# v1.net
KiCad netlist of a schematic drawn in EAGLE
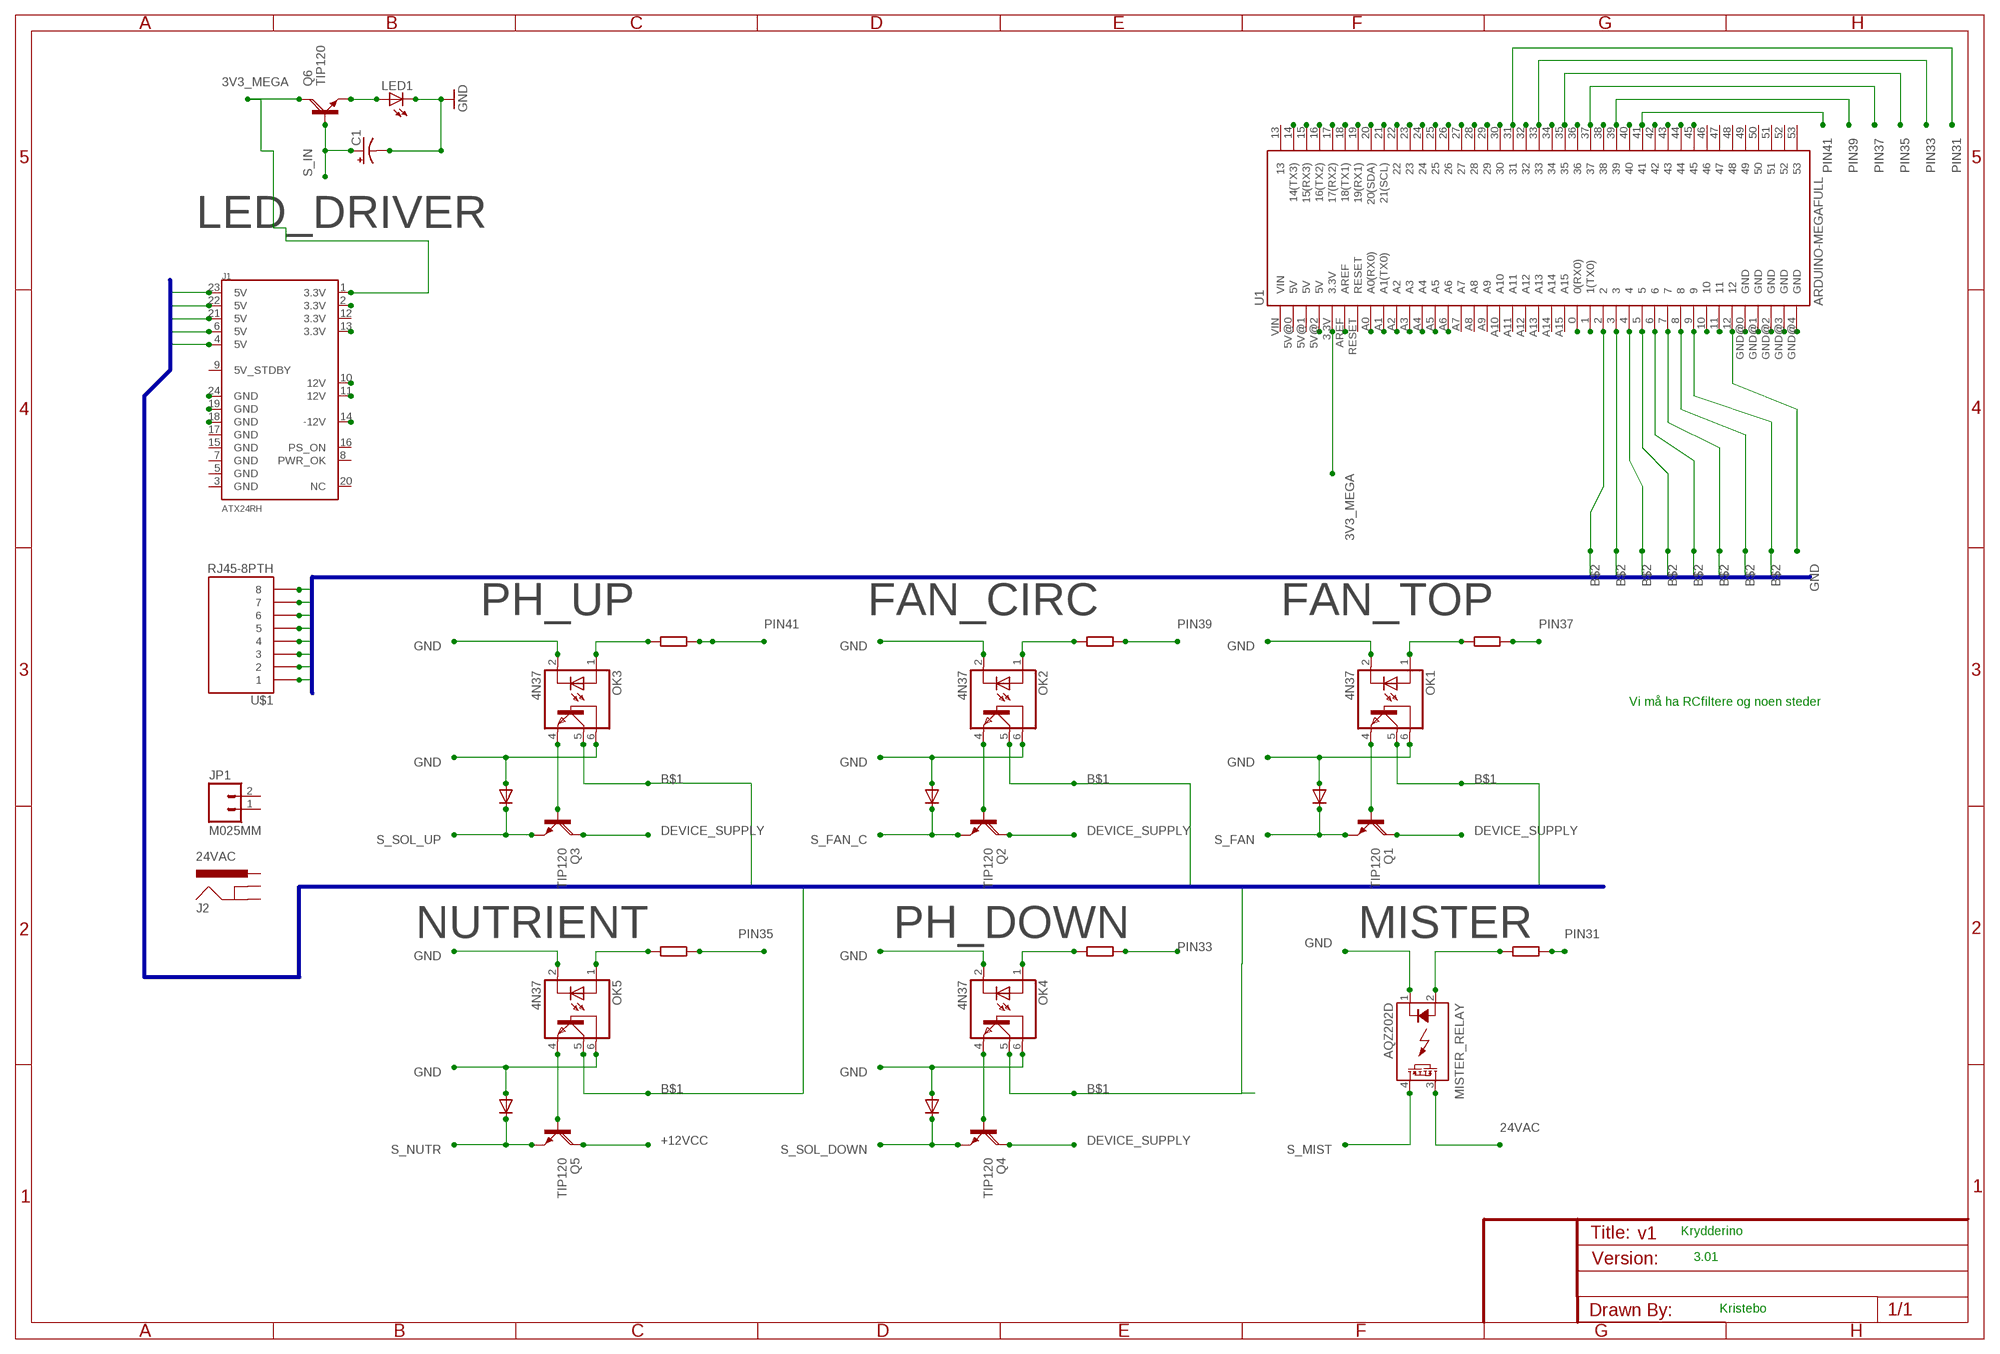
[diagram p0: schematic, sheet 1]

(export (version "E")
  (design (tool "Eeschema 10.0.6"))
  (components
    (comp (ref "C1")
      (value "CAP_POLPTH1")
      (footprint "eagle-import:CPOL-RADIAL-100UF-25V")
      (libsource (lib "eagle-import") (part "CAP_POLPTH1"))
    )
    (comp (ref "J1")
      (value "ATX24RH")
      (footprint "eagle-import:ATX24_RIGHT_ANGLE")
      (libsource (lib "eagle-import") (part "ATX24RH"))
    )
    (comp (ref "J2")
      (value "24VAC")
      (footprint "eagle-import:POWER_JACK_SLOT")
      (libsource (lib "eagle-import") (part "POWER_JACKSLT"))
    )
    (comp (ref "JP1")
      (value "M025MM")
      (footprint "eagle-import:SCREWTERMINAL-5MM-2")
      (libsource (lib "eagle-import") (part "M025MM"))
    )
    (comp (ref "LED1")
      (value "LED3MM")
      (footprint "eagle-import:LED3MM")
      (libsource (lib "eagle-import") (part "LED3MM"))
    )
    (comp (ref "MISTER_RELAY")
      (value "AQZ202D")
      (footprint "eagle-import:AQZ-SIL04")
      (fields (field (name "MF") "AROMAT/ MATSUSHITA"))
      (libsource (lib "eagle-import") (part "AQZ20D2"))
    )
    (comp (ref "OK1")
      (value "4N37")
      (footprint "eagle-import:DIL06")
      (fields (field (name "MF") "FAIRCHILD SEMICONDUCTOR"))
      (libsource (lib "eagle-import") (part "4N37"))
    )
    (comp (ref "OK2")
      (value "4N37")
      (footprint "eagle-import:DIL06")
      (fields (field (name "MF") "FAIRCHILD SEMICONDUCTOR"))
      (libsource (lib "eagle-import") (part "4N37"))
    )
    (comp (ref "OK3")
      (value "4N37")
      (footprint "eagle-import:DIL06")
      (fields (field (name "MF") "FAIRCHILD SEMICONDUCTOR"))
      (libsource (lib "eagle-import") (part "4N37"))
    )
    (comp (ref "OK4")
      (value "4N37")
      (footprint "eagle-import:DIL06")
      (fields (field (name "MF") "FAIRCHILD SEMICONDUCTOR"))
      (libsource (lib "eagle-import") (part "4N37"))
    )
    (comp (ref "OK5")
      (value "4N37")
      (footprint "eagle-import:DIL06")
      (fields (field (name "MF") "FAIRCHILD SEMICONDUCTOR"))
      (libsource (lib "eagle-import") (part "4N37"))
    )
    (comp (ref "Q1")
      (value "TIP120")
      (footprint "eagle-import:TO220AH")
      (libsource (lib "eagle-import") (part "TIP120"))
    )
    (comp (ref "Q2")
      (value "TIP120")
      (footprint "eagle-import:TO220AH")
      (libsource (lib "eagle-import") (part "TIP120"))
    )
    (comp (ref "Q3")
      (value "TIP120")
      (footprint "eagle-import:TO220AH")
      (libsource (lib "eagle-import") (part "TIP120"))
    )
    (comp (ref "Q4")
      (value "TIP120")
      (footprint "eagle-import:TO220AH")
      (libsource (lib "eagle-import") (part "TIP120"))
    )
    (comp (ref "Q5")
      (value "TIP120")
      (footprint "eagle-import:TO220AH")
      (libsource (lib "eagle-import") (part "TIP120"))
    )
    (comp (ref "Q6")
      (value "TIP120")
      (footprint "eagle-import:TO220AH")
      (libsource (lib "eagle-import") (part "TIP120"))
    )
    (comp (ref "U$1")
      (value "RJ45-8PTH")
      (footprint "eagle-import:RJ45-8")
      (libsource (lib "eagle-import") (part "RJ45-8PTH"))
    )
    (comp (ref "U1")
      (value "ARDUINO-MEGAFULL")
      (footprint "eagle-import:ARDUINO_MEGA")
      (libsource (lib "eagle-import") (part "ARDUINO-MEGAFULL"))
    )
  )
  (nets
    (net (code "1") (name "/+12VCC") (class "Default")
      (node (ref "Q5") (pin "C") (pinfunction "C_C") (pintype "passive"))
    )
    (net (code "2") (name "/3V3_MEGA") (class "Default")
      (node (ref "J1") (pin "1") (pinfunction "3.3V_1") (pintype "bidirectional"))
      (node (ref "Q6") (pin "C") (pinfunction "C_C") (pintype "passive"))
      (node (ref "U1") (pin "3.3V") (pinfunction "3.3V_3.3V") (pintype "bidirectional"))
    )
    (net (code "3") (name "/24VAC") (class "Default")
      (node (ref "MISTER_RELAY") (pin "3") (pinfunction "DS1_3") (pintype "passive"))
    )
    (net (code "4") (name "/B$1") (class "Default")
      (node (ref "J1") (pin "21") (pinfunction "5V_21") (pintype "bidirectional"))
      (node (ref "J1") (pin "22") (pinfunction "5V_22") (pintype "bidirectional"))
      (node (ref "J1") (pin "23") (pinfunction "5V_23") (pintype "bidirectional"))
      (node (ref "J1") (pin "4") (pinfunction "5V_4") (pintype "bidirectional"))
      (node (ref "J1") (pin "6") (pinfunction "5V_6") (pintype "bidirectional"))
      (node (ref "OK1") (pin "5") (pinfunction "COL_5") (pintype "passive"))
      (node (ref "OK2") (pin "5") (pinfunction "COL_5") (pintype "passive"))
      (node (ref "OK3") (pin "5") (pinfunction "COL_5") (pintype "passive"))
      (node (ref "OK4") (pin "5") (pinfunction "COL_5") (pintype "passive"))
      (node (ref "OK5") (pin "5") (pinfunction "COL_5") (pintype "passive"))
    )
    (net (code "5") (name "/B$2") (class "Default")
      (node (ref "U$1") (pin "1") (pinfunction "1_1") (pintype "bidirectional"))
      (node (ref "U$1") (pin "2") (pinfunction "2_2") (pintype "bidirectional"))
      (node (ref "U$1") (pin "3") (pinfunction "3_3") (pintype "bidirectional"))
      (node (ref "U$1") (pin "4") (pinfunction "4_4") (pintype "bidirectional"))
      (node (ref "U$1") (pin "5") (pinfunction "5_5") (pintype "bidirectional"))
      (node (ref "U$1") (pin "6") (pinfunction "6_6") (pintype "bidirectional"))
      (node (ref "U$1") (pin "7") (pinfunction "7_7") (pintype "bidirectional"))
      (node (ref "U$1") (pin "8") (pinfunction "8_8") (pintype "bidirectional"))
      (node (ref "U1") (pin "2") (pinfunction "2_2") (pintype "bidirectional"))
      (node (ref "U1") (pin "3") (pinfunction "3_3") (pintype "bidirectional"))
      (node (ref "U1") (pin "4") (pinfunction "4_4") (pintype "bidirectional"))
      (node (ref "U1") (pin "5") (pinfunction "5_5") (pintype "bidirectional"))
      (node (ref "U1") (pin "6") (pinfunction "6_6") (pintype "bidirectional"))
      (node (ref "U1") (pin "7") (pinfunction "7_7") (pintype "bidirectional"))
      (node (ref "U1") (pin "8") (pinfunction "8_8") (pintype "bidirectional"))
      (node (ref "U1") (pin "9") (pinfunction "9_9") (pintype "bidirectional"))
    )
    (net (code "6") (name "/DEVICE_SUPPLY") (class "Default")
      (node (ref "Q1") (pin "C") (pinfunction "C_C") (pintype "passive"))
      (node (ref "Q2") (pin "C") (pinfunction "C_C") (pintype "passive"))
      (node (ref "Q3") (pin "C") (pinfunction "C_C") (pintype "passive"))
      (node (ref "Q4") (pin "C") (pinfunction "C_C") (pintype "passive"))
    )
    (net (code "7") (name "/PIN31") (class "Default")
      (node (ref "OK1") (pin "1") (pinfunction "A_1") (pintype "passive"))
      (node (ref "U1") (pin "31") (pinfunction "31_31") (pintype "bidirectional"))
    )
    (net (code "8") (name "/PIN33") (class "Default")
      (node (ref "OK2") (pin "1") (pinfunction "A_1") (pintype "passive"))
      (node (ref "U1") (pin "33") (pinfunction "33_33") (pintype "bidirectional"))
    )
    (net (code "9") (name "/PIN35") (class "Default")
      (node (ref "OK3") (pin "1") (pinfunction "A_1") (pintype "passive"))
      (node (ref "U1") (pin "35") (pinfunction "35_35") (pintype "bidirectional"))
    )
    (net (code "10") (name "/PIN37") (class "Default")
      (node (ref "OK4") (pin "1") (pinfunction "A_1") (pintype "passive"))
      (node (ref "U1") (pin "37") (pinfunction "37_37") (pintype "bidirectional"))
    )
    (net (code "11") (name "/PIN39") (class "Default")
      (node (ref "OK5") (pin "1") (pinfunction "A_1") (pintype "passive"))
      (node (ref "U1") (pin "39") (pinfunction "39_39") (pintype "bidirectional"))
    )
    (net (code "12") (name "/PIN41") (class "Default")
      (node (ref "MISTER_RELAY") (pin "2") (pinfunction "A_2") (pintype "passive"))
      (node (ref "U1") (pin "41") (pinfunction "41_41") (pintype "bidirectional"))
    )
    (net (code "13") (name "/S_FAN") (class "Default")
      (node (ref "Q1") (pin "E") (pinfunction "E_E") (pintype "passive"))
    )
    (net (code "14") (name "/S_FAN_C") (class "Default")
      (node (ref "Q2") (pin "E") (pinfunction "E_E") (pintype "passive"))
    )
    (net (code "15") (name "/S_IN") (class "Default")
      (node (ref "C1") (pin "1") (pinfunction "+_1") (pintype "passive"))
      (node (ref "Q6") (pin "B") (pinfunction "B_B") (pintype "passive"))
    )
    (net (code "16") (name "/S_MIST") (class "Default")
      (node (ref "MISTER_RELAY") (pin "4") (pinfunction "DS2_4") (pintype "passive"))
    )
    (net (code "17") (name "/S_NUTR") (class "Default")
      (node (ref "Q5") (pin "E") (pinfunction "E_E") (pintype "passive"))
    )
    (net (code "18") (name "/S_SOL_DOWN") (class "Default")
      (node (ref "Q4") (pin "E") (pinfunction "E_E") (pintype "passive"))
    )
    (net (code "19") (name "/S_SOL_UP") (class "Default")
      (node (ref "Q3") (pin "E") (pinfunction "E_E") (pintype "passive"))
    )
    (net (code "20") (name "GND") (class "Default")
      (node (ref "C1") (pin "2") (pinfunction "-_2") (pintype "passive"))
      (node (ref "LED1") (pin "K") (pinfunction "C_K") (pintype "passive"))
      (node (ref "MISTER_RELAY") (pin "1") (pinfunction "K_1") (pintype "passive"))
      (node (ref "OK1") (pin "2") (pinfunction "C_2") (pintype "passive"))
      (node (ref "OK1") (pin "6") (pinfunction "BAS_6") (pintype "passive"))
      (node (ref "OK2") (pin "2") (pinfunction "C_2") (pintype "passive"))
      (node (ref "OK2") (pin "6") (pinfunction "BAS_6") (pintype "passive"))
      (node (ref "OK3") (pin "2") (pinfunction "C_2") (pintype "passive"))
      (node (ref "OK3") (pin "6") (pinfunction "BAS_6") (pintype "passive"))
      (node (ref "OK4") (pin "2") (pinfunction "C_2") (pintype "passive"))
      (node (ref "OK4") (pin "6") (pinfunction "BAS_6") (pintype "passive"))
      (node (ref "OK5") (pin "2") (pinfunction "C_2") (pintype "passive"))
      (node (ref "OK5") (pin "6") (pinfunction "BAS_6") (pintype "passive"))
      (node (ref "U1") (pin "12") (pinfunction "12_12") (pintype "bidirectional"))
    )
    (net (code "21") (name "Net-(LED1-PadA)") (class "Default")
      (node (ref "LED1") (pin "A") (pinfunction "A_A") (pintype "passive"))
      (node (ref "Q6") (pin "E") (pinfunction "E_E") (pintype "passive"))
    )
    (net (code "22") (name "Net-(OK1-EMI)") (class "Default")
      (node (ref "OK1") (pin "4") (pinfunction "EMI_4") (pintype "passive"))
      (node (ref "Q1") (pin "B") (pinfunction "B_B") (pintype "passive"))
    )
    (net (code "23") (name "Net-(OK2-EMI)") (class "Default")
      (node (ref "OK2") (pin "4") (pinfunction "EMI_4") (pintype "passive"))
      (node (ref "Q2") (pin "B") (pinfunction "B_B") (pintype "passive"))
    )
    (net (code "24") (name "Net-(OK3-EMI)") (class "Default")
      (node (ref "OK3") (pin "4") (pinfunction "EMI_4") (pintype "passive"))
      (node (ref "Q3") (pin "B") (pinfunction "B_B") (pintype "passive"))
    )
    (net (code "25") (name "Net-(OK4-EMI)") (class "Default")
      (node (ref "OK4") (pin "4") (pinfunction "EMI_4") (pintype "passive"))
      (node (ref "Q4") (pin "B") (pinfunction "B_B") (pintype "passive"))
    )
    (net (code "26") (name "Net-(OK5-EMI)") (class "Default")
      (node (ref "OK5") (pin "4") (pinfunction "EMI_4") (pintype "passive"))
      (node (ref "Q5") (pin "B") (pinfunction "B_B") (pintype "passive"))
    )
    (net (code "27") (name "unconnected-(J1--12V-Pad14)") (class "Default")
      (node (ref "J1") (pin "14") (pinfunction "-12V_14") (pintype "bidirectional"))
    )
    (net (code "28") (name "unconnected-(J1-3.3V-Pad2)") (class "Default")
      (node (ref "J1") (pin "2") (pinfunction "3.3V_2") (pintype "bidirectional"))
    )
    (net (code "29") (name "unconnected-(J1-3.3V-Pad12)") (class "Default")
      (node (ref "J1") (pin "12") (pinfunction "3.3V_12") (pintype "bidirectional"))
    )
    (net (code "30") (name "unconnected-(J1-3.3V-Pad13)") (class "Default")
      (node (ref "J1") (pin "13") (pinfunction "3.3V_13") (pintype "bidirectional"))
    )
    (net (code "31") (name "unconnected-(J1-5V_STDBY-Pad9)") (class "Default")
      (node (ref "J1") (pin "9") (pinfunction "5V_STDBY_9") (pintype "bidirectional"))
    )
    (net (code "32") (name "unconnected-(J1-12V-Pad10)") (class "Default")
      (node (ref "J1") (pin "10") (pinfunction "12V_10") (pintype "bidirectional"))
    )
    (net (code "33") (name "unconnected-(J1-12V-Pad11)") (class "Default")
      (node (ref "J1") (pin "11") (pinfunction "12V_11") (pintype "bidirectional"))
    )
    (net (code "34") (name "unconnected-(J1-GND-Pad3)") (class "Default")
      (node (ref "J1") (pin "3") (pinfunction "GND_3") (pintype "bidirectional"))
    )
    (net (code "35") (name "unconnected-(J1-GND-Pad5)") (class "Default")
      (node (ref "J1") (pin "5") (pinfunction "GND_5") (pintype "bidirectional"))
    )
    (net (code "36") (name "unconnected-(J1-GND-Pad7)") (class "Default")
      (node (ref "J1") (pin "7") (pinfunction "GND_7") (pintype "bidirectional"))
    )
    (net (code "37") (name "unconnected-(J1-GND-Pad15)") (class "Default")
      (node (ref "J1") (pin "15") (pinfunction "GND_15") (pintype "bidirectional"))
    )
    (net (code "38") (name "unconnected-(J1-GND-Pad17)") (class "Default")
      (node (ref "J1") (pin "17") (pinfunction "GND_17") (pintype "bidirectional"))
    )
    (net (code "39") (name "unconnected-(J1-GND-Pad18)") (class "Default")
      (node (ref "J1") (pin "18") (pinfunction "GND_18") (pintype "bidirectional"))
    )
    (net (code "40") (name "unconnected-(J1-GND-Pad19)") (class "Default")
      (node (ref "J1") (pin "19") (pinfunction "GND_19") (pintype "bidirectional"))
    )
    (net (code "41") (name "unconnected-(J1-GND-Pad24)") (class "Default")
      (node (ref "J1") (pin "24") (pinfunction "GND_24") (pintype "bidirectional"))
    )
    (net (code "42") (name "unconnected-(J1-NC-Pad20)") (class "Default")
      (node (ref "J1") (pin "20") (pinfunction "NC_20") (pintype "bidirectional"))
    )
    (net (code "43") (name "unconnected-(J1-PS_ON-Pad16)") (class "Default")
      (node (ref "J1") (pin "16") (pinfunction "PS_ON_16") (pintype "bidirectional"))
    )
    (net (code "44") (name "unconnected-(J1-PWR_OK-Pad8)") (class "Default")
      (node (ref "J1") (pin "8") (pinfunction "PWR_OK_8") (pintype "bidirectional"))
    )
    (net (code "45") (name "unconnected-(J2-GND-PadGND@2)") (class "Default")
      (node (ref "J2") (pin "GND@2") (pinfunction "GND_GND@2") (pintype "bidirectional"))
    )
    (net (code "46") (name "unconnected-(J2-GNDBREAK-PadGND@1)") (class "Default")
      (node (ref "J2") (pin "GND@1") (pinfunction "GNDBREAK_GND@1") (pintype "bidirectional"))
    )
    (net (code "47") (name "unconnected-(J2-PadPWR)") (class "Default")
      (node (ref "J2") (pin "PWR") (pinfunction "PWR_PWR") (pintype "bidirectional"))
    )
    (net (code "48") (name "unconnected-(JP1-Pad1)") (class "Default")
      (node (ref "JP1") (pin "1") (pinfunction "1_1") (pintype "passive"))
    )
    (net (code "49") (name "unconnected-(JP1-Pad2)") (class "Default")
      (node (ref "JP1") (pin "2") (pinfunction "2_2") (pintype "passive"))
    )
    (net (code "50") (name "unconnected-(U1-0(RX0)-Pad0)") (class "Default")
      (node (ref "U1") (pin "0") (pinfunction "0(RX0)_0") (pintype "bidirectional"))
    )
    (net (code "51") (name "unconnected-(U1-1(TX0)-Pad1)") (class "Default")
      (node (ref "U1") (pin "1") (pinfunction "1(TX0)_1") (pintype "bidirectional"))
    )
    (net (code "52") (name "unconnected-(U1-5V-Pad5V@0)") (class "Default")
      (node (ref "U1") (pin "5V@0") (pinfunction "5V_5V@0") (pintype "bidirectional"))
    )
    (net (code "53") (name "unconnected-(U1-5V-Pad5V@1)") (class "Default")
      (node (ref "U1") (pin "5V@1") (pinfunction "5V_5V@1") (pintype "bidirectional"))
    )
    (net (code "54") (name "unconnected-(U1-5V-Pad5V@2)") (class "Default")
      (node (ref "U1") (pin "5V@2") (pinfunction "5V_5V@2") (pintype "bidirectional"))
    )
    (net (code "55") (name "unconnected-(U1-14(TX3)-Pad14)") (class "Default")
      (node (ref "U1") (pin "14") (pinfunction "14(TX3)_14") (pintype "bidirectional"))
    )
    (net (code "56") (name "unconnected-(U1-15(RX3)-Pad15)") (class "Default")
      (node (ref "U1") (pin "15") (pinfunction "15(RX3)_15") (pintype "bidirectional"))
    )
    (net (code "57") (name "unconnected-(U1-16(TX2)-Pad16)") (class "Default")
      (node (ref "U1") (pin "16") (pinfunction "16(TX2)_16") (pintype "bidirectional"))
    )
    (net (code "58") (name "unconnected-(U1-17(RX2)-Pad17)") (class "Default")
      (node (ref "U1") (pin "17") (pinfunction "17(RX2)_17") (pintype "bidirectional"))
    )
    (net (code "59") (name "unconnected-(U1-18(TX1)-Pad18)") (class "Default")
      (node (ref "U1") (pin "18") (pinfunction "18(TX1)_18") (pintype "bidirectional"))
    )
    (net (code "60") (name "unconnected-(U1-19(RX1)-Pad19)") (class "Default")
      (node (ref "U1") (pin "19") (pinfunction "19(RX1)_19") (pintype "bidirectional"))
    )
    (net (code "61") (name "unconnected-(U1-20(SDA)-Pad20)") (class "Default")
      (node (ref "U1") (pin "20") (pinfunction "20(SDA)_20") (pintype "bidirectional"))
    )
    (net (code "62") (name "unconnected-(U1-21(SCL)-Pad21)") (class "Default")
      (node (ref "U1") (pin "21") (pinfunction "21(SCL)_21") (pintype "bidirectional"))
    )
    (net (code "63") (name "unconnected-(U1-A0(RX0)-PadA0)") (class "Default")
      (node (ref "U1") (pin "A0") (pinfunction "A0(RX0)_A0") (pintype "bidirectional"))
    )
    (net (code "64") (name "unconnected-(U1-A1(TX0)-PadA1)") (class "Default")
      (node (ref "U1") (pin "A1") (pinfunction "A1(TX0)_A1") (pintype "bidirectional"))
    )
    (net (code "65") (name "unconnected-(U1-GND-PadGND@0)") (class "Default")
      (node (ref "U1") (pin "GND@0") (pinfunction "GND_GND@0") (pintype "bidirectional"))
    )
    (net (code "66") (name "unconnected-(U1-GND-PadGND@1)") (class "Default")
      (node (ref "U1") (pin "GND@1") (pinfunction "GND_GND@1") (pintype "bidirectional"))
    )
    (net (code "67") (name "unconnected-(U1-GND-PadGND@2)") (class "Default")
      (node (ref "U1") (pin "GND@2") (pinfunction "GND_GND@2") (pintype "bidirectional"))
    )
    (net (code "68") (name "unconnected-(U1-GND-PadGND@3)") (class "Default")
      (node (ref "U1") (pin "GND@3") (pinfunction "GND_GND@3") (pintype "bidirectional"))
    )
    (net (code "69") (name "unconnected-(U1-GND-PadGND@4)") (class "Default")
      (node (ref "U1") (pin "GND@4") (pinfunction "GND_GND@4") (pintype "bidirectional"))
    )
    (net (code "70") (name "unconnected-(U1-Pad10)") (class "Default")
      (node (ref "U1") (pin "10") (pinfunction "10_10") (pintype "bidirectional"))
    )
    (net (code "71") (name "unconnected-(U1-Pad11)") (class "Default")
      (node (ref "U1") (pin "11") (pinfunction "11_11") (pintype "bidirectional"))
    )
    (net (code "72") (name "unconnected-(U1-Pad13)") (class "Default")
      (node (ref "U1") (pin "13") (pinfunction "13_13") (pintype "bidirectional"))
    )
    (net (code "73") (name "unconnected-(U1-Pad22)") (class "Default")
      (node (ref "U1") (pin "22") (pinfunction "22_22") (pintype "bidirectional"))
    )
    (net (code "74") (name "unconnected-(U1-Pad23)") (class "Default")
      (node (ref "U1") (pin "23") (pinfunction "23_23") (pintype "bidirectional"))
    )
    (net (code "75") (name "unconnected-(U1-Pad24)") (class "Default")
      (node (ref "U1") (pin "24") (pinfunction "24_24") (pintype "bidirectional"))
    )
    (net (code "76") (name "unconnected-(U1-Pad25)") (class "Default")
      (node (ref "U1") (pin "25") (pinfunction "25_25") (pintype "bidirectional"))
    )
    (net (code "77") (name "unconnected-(U1-Pad26)") (class "Default")
      (node (ref "U1") (pin "26") (pinfunction "26_26") (pintype "bidirectional"))
    )
    (net (code "78") (name "unconnected-(U1-Pad27)") (class "Default")
      (node (ref "U1") (pin "27") (pinfunction "27_27") (pintype "bidirectional"))
    )
    (net (code "79") (name "unconnected-(U1-Pad28)") (class "Default")
      (node (ref "U1") (pin "28") (pinfunction "28_28") (pintype "bidirectional"))
    )
    (net (code "80") (name "unconnected-(U1-Pad29)") (class "Default")
      (node (ref "U1") (pin "29") (pinfunction "29_29") (pintype "bidirectional"))
    )
    (net (code "81") (name "unconnected-(U1-Pad30)") (class "Default")
      (node (ref "U1") (pin "30") (pinfunction "30_30") (pintype "bidirectional"))
    )
    (net (code "82") (name "unconnected-(U1-Pad32)") (class "Default")
      (node (ref "U1") (pin "32") (pinfunction "32_32") (pintype "bidirectional"))
    )
    (net (code "83") (name "unconnected-(U1-Pad34)") (class "Default")
      (node (ref "U1") (pin "34") (pinfunction "34_34") (pintype "bidirectional"))
    )
    (net (code "84") (name "unconnected-(U1-Pad36)") (class "Default")
      (node (ref "U1") (pin "36") (pinfunction "36_36") (pintype "bidirectional"))
    )
    (net (code "85") (name "unconnected-(U1-Pad38)") (class "Default")
      (node (ref "U1") (pin "38") (pinfunction "38_38") (pintype "bidirectional"))
    )
    (net (code "86") (name "unconnected-(U1-Pad40)") (class "Default")
      (node (ref "U1") (pin "40") (pinfunction "40_40") (pintype "bidirectional"))
    )
    (net (code "87") (name "unconnected-(U1-Pad42)") (class "Default")
      (node (ref "U1") (pin "42") (pinfunction "42_42") (pintype "bidirectional"))
    )
    (net (code "88") (name "unconnected-(U1-Pad43)") (class "Default")
      (node (ref "U1") (pin "43") (pinfunction "43_43") (pintype "bidirectional"))
    )
    (net (code "89") (name "unconnected-(U1-Pad44)") (class "Default")
      (node (ref "U1") (pin "44") (pinfunction "44_44") (pintype "bidirectional"))
    )
    (net (code "90") (name "unconnected-(U1-Pad45)") (class "Default")
      (node (ref "U1") (pin "45") (pinfunction "45_45") (pintype "bidirectional"))
    )
    (net (code "91") (name "unconnected-(U1-Pad46)") (class "Default")
      (node (ref "U1") (pin "46") (pinfunction "46_46") (pintype "bidirectional"))
    )
    (net (code "92") (name "unconnected-(U1-Pad47)") (class "Default")
      (node (ref "U1") (pin "47") (pinfunction "47_47") (pintype "bidirectional"))
    )
    (net (code "93") (name "unconnected-(U1-Pad48)") (class "Default")
      (node (ref "U1") (pin "48") (pinfunction "48_48") (pintype "bidirectional"))
    )
    (net (code "94") (name "unconnected-(U1-Pad49)") (class "Default")
      (node (ref "U1") (pin "49") (pinfunction "49_49") (pintype "bidirectional"))
    )
    (net (code "95") (name "unconnected-(U1-Pad50)") (class "Default")
      (node (ref "U1") (pin "50") (pinfunction "50_50") (pintype "bidirectional"))
    )
    (net (code "96") (name "unconnected-(U1-Pad51)") (class "Default")
      (node (ref "U1") (pin "51") (pinfunction "51_51") (pintype "bidirectional"))
    )
    (net (code "97") (name "unconnected-(U1-Pad52)") (class "Default")
      (node (ref "U1") (pin "52") (pinfunction "52_52") (pintype "bidirectional"))
    )
    (net (code "98") (name "unconnected-(U1-Pad53)") (class "Default")
      (node (ref "U1") (pin "53") (pinfunction "53_53") (pintype "bidirectional"))
    )
    (net (code "99") (name "unconnected-(U1-PadA2)") (class "Default")
      (node (ref "U1") (pin "A2") (pinfunction "A2_A2") (pintype "bidirectional"))
    )
    (net (code "100") (name "unconnected-(U1-PadA3)") (class "Default")
      (node (ref "U1") (pin "A3") (pinfunction "A3_A3") (pintype "bidirectional"))
    )
    (net (code "101") (name "unconnected-(U1-PadA4)") (class "Default")
      (node (ref "U1") (pin "A4") (pinfunction "A4_A4") (pintype "bidirectional"))
    )
    (net (code "102") (name "unconnected-(U1-PadA5)") (class "Default")
      (node (ref "U1") (pin "A5") (pinfunction "A5_A5") (pintype "bidirectional"))
    )
    (net (code "103") (name "unconnected-(U1-PadA6)") (class "Default")
      (node (ref "U1") (pin "A6") (pinfunction "A6_A6") (pintype "bidirectional"))
    )
    (net (code "104") (name "unconnected-(U1-PadA7)") (class "Default")
      (node (ref "U1") (pin "A7") (pinfunction "A7_A7") (pintype "bidirectional"))
    )
    (net (code "105") (name "unconnected-(U1-PadA8)") (class "Default")
      (node (ref "U1") (pin "A8") (pinfunction "A8_A8") (pintype "bidirectional"))
    )
    (net (code "106") (name "unconnected-(U1-PadA9)") (class "Default")
      (node (ref "U1") (pin "A9") (pinfunction "A9_A9") (pintype "bidirectional"))
    )
    (net (code "107") (name "unconnected-(U1-PadA10)") (class "Default")
      (node (ref "U1") (pin "A10") (pinfunction "A10_A10") (pintype "bidirectional"))
    )
    (net (code "108") (name "unconnected-(U1-PadA11)") (class "Default")
      (node (ref "U1") (pin "A11") (pinfunction "A11_A11") (pintype "bidirectional"))
    )
    (net (code "109") (name "unconnected-(U1-PadA12)") (class "Default")
      (node (ref "U1") (pin "A12") (pinfunction "A12_A12") (pintype "bidirectional"))
    )
    (net (code "110") (name "unconnected-(U1-PadA13)") (class "Default")
      (node (ref "U1") (pin "A13") (pinfunction "A13_A13") (pintype "bidirectional"))
    )
    (net (code "111") (name "unconnected-(U1-PadA14)") (class "Default")
      (node (ref "U1") (pin "A14") (pinfunction "A14_A14") (pintype "bidirectional"))
    )
    (net (code "112") (name "unconnected-(U1-PadA15)") (class "Default")
      (node (ref "U1") (pin "A15") (pinfunction "A15_A15") (pintype "bidirectional"))
    )
    (net (code "113") (name "unconnected-(U1-PadAREF)") (class "Default")
      (node (ref "U1") (pin "AREF") (pinfunction "AREF_AREF") (pintype "bidirectional"))
    )
    (net (code "114") (name "unconnected-(U1-PadRESET)") (class "Default")
      (node (ref "U1") (pin "RESET") (pinfunction "RESET_RESET") (pintype "bidirectional"))
    )
    (net (code "115") (name "unconnected-(U1-PadVIN)") (class "Default")
      (node (ref "U1") (pin "VIN") (pinfunction "VIN_VIN") (pintype "bidirectional"))
    )
  )
)
